# NNLightSwitcher_WirelessCharger.net
KiCad netlist of a schematic drawn in Altium Designer
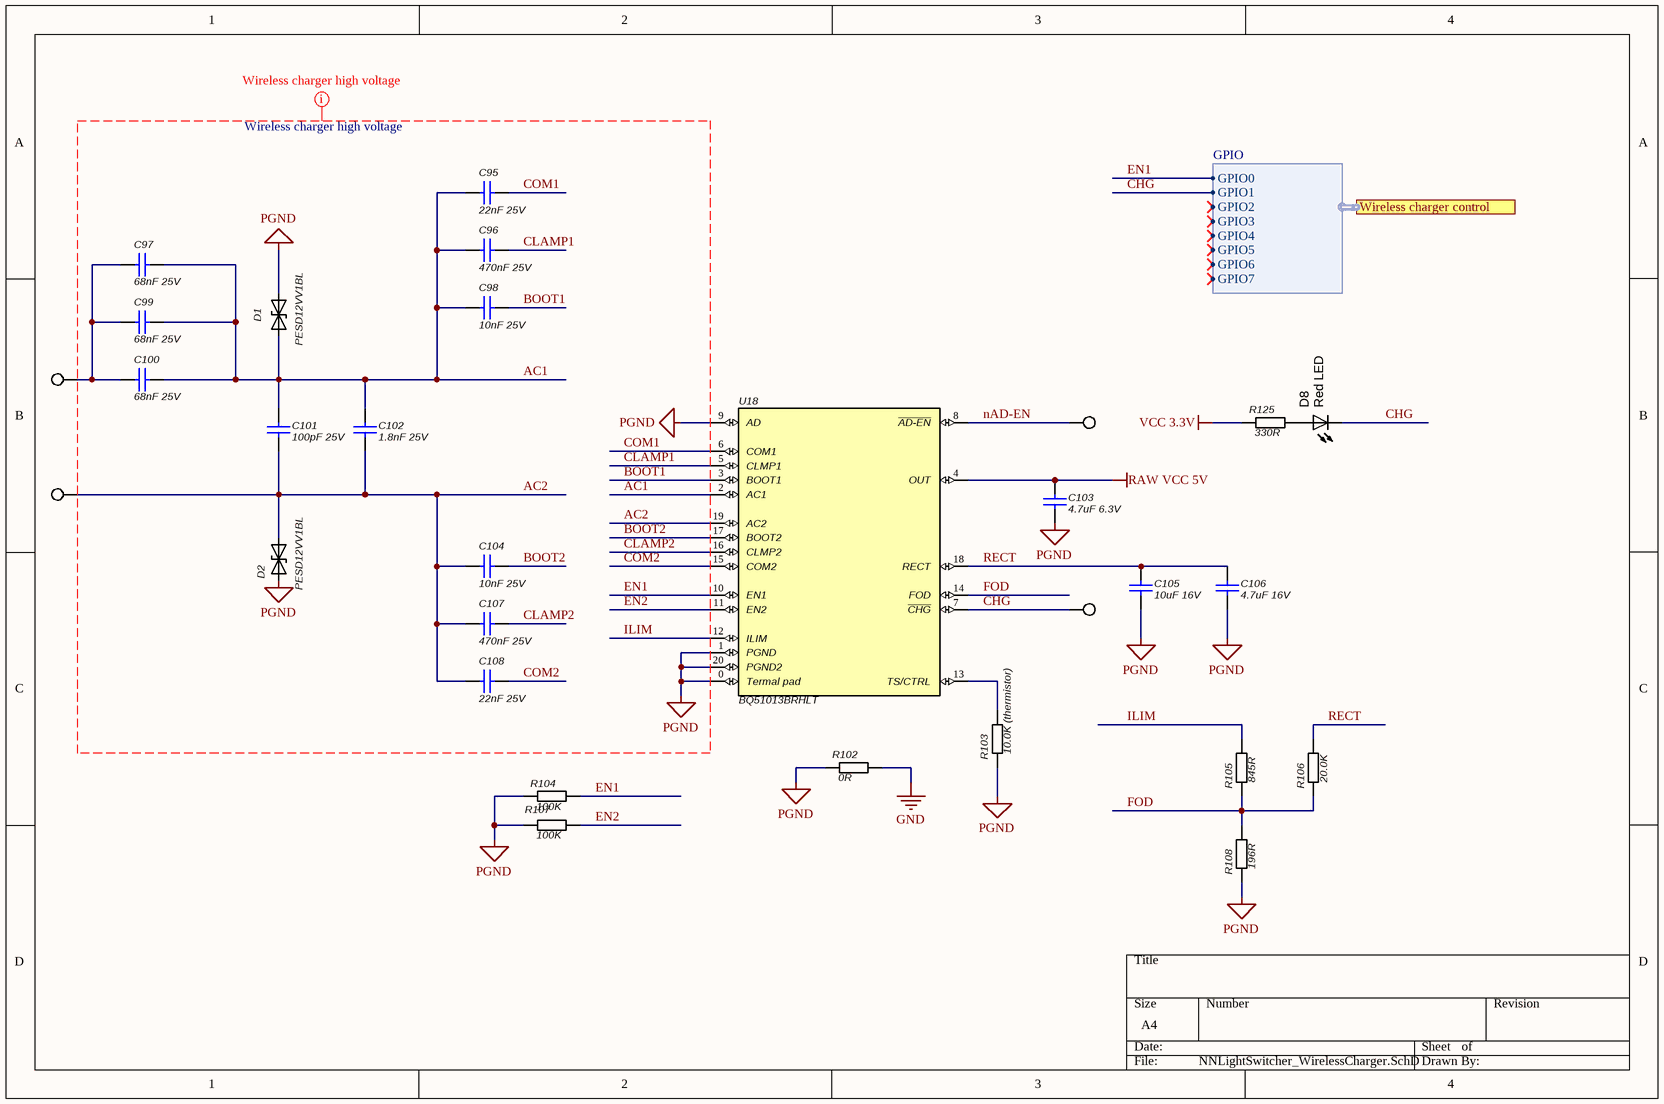
[diagram p0: NNLightSwitcher_WirelessCharger.SchDoc]

(export (version "E")
  (design (tool "Eeschema 10.0.6"))
  (components
    (comp (ref "C95")
      (value "22nF 25V")
      (footprint "0402")
      (description "GRM155R71E223KA61D")
      (fields (field (name "TOLERANCE") "10%") (field (name "VOLTAGE") "25V"))
      (libsource (lib "NNLightSwitcher") (part "Capacitor 22nF 25V"))
    )
    (comp (ref "C96")
      (value "470nF 25V")
      (footprint "0402")
      (description "GRM188R71E474KA12D")
      (fields (field (name "TOLERANCE") "10%") (field (name "VOLTAGE") "50V"))
      (libsource (lib "NNLightSwitcher") (part "Capacitor 470nF 25V"))
    )
    (comp (ref "C97")
      (value "68nF 25V")
      (footprint "*0603")
      (description "CAP CER 0.068UF 25V X7R 0603CC0603KRX7R8BB683")
      (fields (field (name "TOLERANCE") "10%") (field (name "VOLTAGE") "25V"))
      (libsource (lib "NNLightSwitcher") (part "Capacitor 68nF 25V"))
    )
    (comp (ref "C98")
      (value "10nF 25V")
      (footprint "0402")
      (description "GRM155R71E103KA01D")
      (fields (field (name "TOLERANCE") "10%") (field (name "VOLTAGE") "25V"))
      (libsource (lib "NNLightSwitcher") (part "Capacitor 10nF 25V"))
    )
    (comp (ref "C99")
      (value "68nF 25V")
      (footprint "*0603")
      (description "CAP CER 0.068UF 25V X7R 0603CC0603KRX7R8BB683")
      (fields (field (name "TOLERANCE") "10%") (field (name "VOLTAGE") "25V"))
      (libsource (lib "NNLightSwitcher") (part "Capacitor 68nF 25V"))
    )
    (comp (ref "C100")
      (value "68nF 25V")
      (footprint "*0603")
      (description "CAP CER 0.068UF 25V X7R 0603CC0603KRX7R8BB683")
      (fields (field (name "TOLERANCE") "10%") (field (name "VOLTAGE") "25V"))
      (libsource (lib "NNLightSwitcher") (part "Capacitor 68nF 25V"))
    )
    (comp (ref "C101")
      (value "100pF 25V")
      (footprint "0402")
      (description "GRM033R71E101KA01D")
      (fields (field (name "TOLERANCE") "10%") (field (name "VOLTAGE") "25V"))
      (libsource (lib "NNLightSwitcher") (part "Capacitor 100pF 25V"))
    )
    (comp (ref "C102")
      (value "1.8nF 25V")
      (footprint "0402")
      (description "GRM155R71H182KA01D")
      (fields (field (name "TOLERANCE") "10%") (field (name "VOLTAGE") "50V"))
      (libsource (lib "NNLightSwitcher") (part "Capacitor 1.8nF 50V"))
    )
    (comp (ref "C103")
      (value "4.7uF 6.3V")
      (footprint "*0603")
      (libsource (lib "NNLightSwitcher") (part "Capacitor 4.7uF 6.3V"))
    )
    (comp (ref "C104")
      (value "10nF 25V")
      (footprint "0402")
      (description "GRM155R71E103KA01D")
      (fields (field (name "TOLERANCE") "10%") (field (name "VOLTAGE") "25V"))
      (libsource (lib "NNLightSwitcher") (part "Capacitor 10nF 25V"))
    )
    (comp (ref "C105")
      (value "10uF 16V")
      (footprint "*0603")
      (description "EMK107BBJ106MA-T")
      (fields (field (name "TOLERANCE") "20%"))
      (libsource (lib "NNLightSwitcher") (part "Capacitor 10uF 16V"))
    )
    (comp (ref "C106")
      (value "4.7uF 16V")
      (footprint "*0603")
      (description "GRM188R61C475KAAJ")
      (fields (field (name "TOLERANCE") "10%"))
      (libsource (lib "NNLightSwitcher") (part "Capacitor 4.7uF 16V"))
    )
    (comp (ref "C107")
      (value "470nF 25V")
      (footprint "0402")
      (description "GRM188R71E474KA12D")
      (fields (field (name "TOLERANCE") "10%") (field (name "VOLTAGE") "50V"))
      (libsource (lib "NNLightSwitcher") (part "Capacitor 470nF 25V"))
    )
    (comp (ref "C108")
      (value "22nF 25V")
      (footprint "0402")
      (description "GRM155R71E223KA61D")
      (fields (field (name "TOLERANCE") "10%") (field (name "VOLTAGE") "25V"))
      (libsource (lib "NNLightSwitcher") (part "Capacitor 22nF 25V"))
    )
    (comp (ref "D1")
      (value "PESD12VV1BL")
      (footprint "*SOD882(T)")
      (description "ESD Suppressor TVS 30KV")
      (libsource (lib "NNLightSwitcher") (part "PESD12VV1BL"))
    )
    (comp (ref "D2")
      (value "PESD12VV1BL")
      (footprint "*SOD882(T)")
      (description "ESD Suppressor TVS 30KV")
      (libsource (lib "NNLightSwitcher") (part "PESD12VV1BL"))
    )
    (comp (ref "D8")
      (value "Red LED")
      (footprint "*LED_SML-P11UTT86R_SML-P11MTT86(Primary)")
      (description "LED red 0402")
      (libsource (lib "NNLightSwitcher") (part "APHHS1005SURCK"))
    )
    (comp (ref "R102")
      (value "0R")
      (footprint "0402")
      (libsource (lib "NNLightSwitcher") (part "Resistor 0R"))
    )
    (comp (ref "R103")
      (value "10.0K (thermistor)")
      (footprint "0402")
      (description "thermistor")
      (libsource (lib "NNLightSwitcher") (part "Resistor 10.0K"))
    )
    (comp (ref "R104")
      (value "100K")
      (footprint "0402")
      (libsource (lib "NNLightSwitcher") (part "Resistor 100K"))
    )
    (comp (ref "R105")
      (value "845R")
      (footprint "0402")
      (libsource (lib "NNLightSwitcher") (part "Resistor 845R"))
    )
    (comp (ref "R106")
      (value "20.0K")
      (footprint "0402")
      (libsource (lib "NNLightSwitcher") (part "Resistor 20.0K"))
    )
    (comp (ref "R107")
      (value "100K")
      (footprint "0402")
      (libsource (lib "NNLightSwitcher") (part "Resistor 100K"))
    )
    (comp (ref "R108")
      (value "196R")
      (footprint "0402")
      (libsource (lib "NNLightSwitcher") (part "Resistor 196R"))
    )
    (comp (ref "R125")
      (value "330R")
      (footprint "0402")
      (libsource (lib "NNLightSwitcher") (part "Resistor 330R"))
    )
    (comp (ref "TP56")
      (value "Test point")
      (footprint "Connection")
      (description "Test Point, Miniature, SMT")
      (libsource (lib "NNLightSwitcher") (part "Test point"))
    )
    (comp (ref "TP57")
      (value "Test point")
      (footprint "Testpoint_with_pad")
      (description "Test Point, Miniature, SMT")
      (libsource (lib "NNLightSwitcher") (part "Test point"))
    )
    (comp (ref "TP58")
      (value "Test point")
      (footprint "Connection")
      (description "Test Point, Miniature, SMT")
      (libsource (lib "NNLightSwitcher") (part "Test point"))
    )
    (comp (ref "TP59")
      (value "Test point")
      (footprint "Testpoint_Keystone_Miniature")
      (description "Test Point, Miniature, SMT")
      (libsource (lib "NNLightSwitcher") (part "Test point"))
    )
    (comp (ref "U18")
      (value "BQ51013BRHLT")
      (footprint "*QFN-20(VQFN-20)")
      (description "WPC 1.1 Compatible Fully Integrated Wireless Power Receiver IC 20-VQFN")
      (libsource (lib "NNLightSwitcher") (part "BQ51013BRHLT"))
    )
  )
  (nets
    (net (code "2") (name "/AC1") (class "Default")
      (node (ref "C100") (pin "1") (pinfunction "1_1") (pintype "passive"))
      (node (ref "C101") (pin "1") (pinfunction "1_1") (pintype "passive"))
      (node (ref "C102") (pin "1") (pinfunction "1_1") (pintype "passive"))
      (node (ref "C95") (pin "2") (pinfunction "2_2") (pintype "passive"))
      (node (ref "C96") (pin "2") (pinfunction "2_2") (pintype "passive"))
      (node (ref "C97") (pin "1") (pinfunction "1_1") (pintype "passive"))
      (node (ref "C98") (pin "2") (pinfunction "2_2") (pintype "passive"))
      (node (ref "C99") (pin "1") (pinfunction "1_1") (pintype "passive"))
      (node (ref "D1") (pin "2") (pinfunction "A_2") (pintype "passive"))
      (node (ref "U18") (pin "2") (pinfunction "AC1_2") (pintype "bidirectional"))
    )
    (net (code "3") (name "/AC2") (class "Default")
      (node (ref "C101") (pin "2") (pinfunction "2_2") (pintype "passive"))
      (node (ref "C102") (pin "2") (pinfunction "2_2") (pintype "passive"))
      (node (ref "C104") (pin "2") (pinfunction "2_2") (pintype "passive"))
      (node (ref "C107") (pin "2") (pinfunction "2_2") (pintype "passive"))
      (node (ref "C108") (pin "2") (pinfunction "2_2") (pintype "passive"))
      (node (ref "D2") (pin "1") (pinfunction "K_1") (pintype "passive"))
      (node (ref "TP58") (pin "1") (pintype "passive"))
      (node (ref "U18") (pin "19") (pinfunction "AC2_19") (pintype "bidirectional"))
    )
    (net (code "4") (name "/BOOT1") (class "Default")
      (node (ref "C98") (pin "1") (pinfunction "1_1") (pintype "passive"))
      (node (ref "U18") (pin "3") (pinfunction "BOOT1_3") (pintype "bidirectional"))
    )
    (net (code "5") (name "/BOOT2") (class "Default")
      (node (ref "C104") (pin "1") (pinfunction "1_1") (pintype "passive"))
      (node (ref "U18") (pin "17") (pinfunction "BOOT2_17") (pintype "bidirectional"))
    )
    (net (code "6") (name "/CHG") (class "Default")
      (node (ref "D8") (pin "C") (pinfunction "C_C") (pintype "passive"))
      (node (ref "TP59") (pin "1") (pintype "passive"))
      (node (ref "U18") (pin "7") (pinfunction "~{CHG}_7") (pintype "bidirectional"))
    )
    (net (code "7") (name "/CLAMP1") (class "Default")
      (node (ref "C96") (pin "1") (pinfunction "1_1") (pintype "passive"))
      (node (ref "U18") (pin "5") (pinfunction "CLMP1_5") (pintype "bidirectional"))
    )
    (net (code "8") (name "/CLAMP2") (class "Default")
      (node (ref "C107") (pin "1") (pinfunction "1_1") (pintype "passive"))
      (node (ref "U18") (pin "16") (pinfunction "CLMP2_16") (pintype "bidirectional"))
    )
    (net (code "9") (name "/COM1") (class "Default")
      (node (ref "C95") (pin "1") (pinfunction "1_1") (pintype "passive"))
      (node (ref "U18") (pin "6") (pinfunction "COM1_6") (pintype "bidirectional"))
    )
    (net (code "10") (name "/COM2") (class "Default")
      (node (ref "C108") (pin "1") (pinfunction "1_1") (pintype "passive"))
      (node (ref "U18") (pin "15") (pinfunction "COM2_15") (pintype "bidirectional"))
    )
    (net (code "11") (name "/EN1") (class "Default")
      (node (ref "R104") (pin "2") (pinfunction "2_2") (pintype "passive"))
      (node (ref "U18") (pin "10") (pinfunction "EN1_10") (pintype "bidirectional"))
    )
    (net (code "12") (name "/EN2") (class "Default")
      (node (ref "R107") (pin "2") (pinfunction "2_2") (pintype "passive"))
      (node (ref "U18") (pin "11") (pinfunction "EN2_11") (pintype "bidirectional"))
    )
    (net (code "13") (name "/FOD") (class "Default")
      (node (ref "R105") (pin "1") (pinfunction "1_1") (pintype "passive"))
      (node (ref "R106") (pin "1") (pinfunction "1_1") (pintype "passive"))
      (node (ref "R108") (pin "2") (pinfunction "2_2") (pintype "passive"))
      (node (ref "U18") (pin "14") (pinfunction "FOD_14") (pintype "bidirectional"))
    )
    (net (code "14") (name "/ILIM") (class "Default")
      (node (ref "R105") (pin "2") (pinfunction "2_2") (pintype "passive"))
      (node (ref "U18") (pin "12") (pinfunction "ILIM_12") (pintype "bidirectional"))
    )
    (net (code "15") (name "/RECT") (class "Default")
      (node (ref "C105") (pin "2") (pinfunction "2_2") (pintype "passive"))
      (node (ref "C106") (pin "1") (pinfunction "1_1") (pintype "passive"))
      (node (ref "R106") (pin "2") (pinfunction "2_2") (pintype "passive"))
      (node (ref "U18") (pin "18") (pinfunction "RECT_18") (pintype "bidirectional"))
    )
    (net (code "16") (name "/nAD-EN") (class "Default")
      (node (ref "TP57") (pin "1") (pintype "passive"))
      (node (ref "U18") (pin "8") (pinfunction "~{AD-EN}_8") (pintype "bidirectional"))
    )
    (net (code "18") (name "GND") (class "Default")
      (node (ref "R102") (pin "2") (pinfunction "2_2") (pintype "passive"))
    )
    (net (code "19") (name "Net-(C100-Pad2)") (class "Default")
      (node (ref "C100") (pin "2") (pinfunction "2_2") (pintype "passive"))
      (node (ref "C97") (pin "2") (pinfunction "2_2") (pintype "passive"))
      (node (ref "C99") (pin "2") (pinfunction "2_2") (pintype "passive"))
      (node (ref "TP56") (pin "1") (pintype "passive"))
    )
    (net (code "20") (name "Net-(D8-PadA)") (class "Default")
      (node (ref "D8") (pin "A") (pinfunction "A_A") (pintype "passive"))
      (node (ref "R125") (pin "2") (pinfunction "2_2") (pintype "passive"))
    )
    (net (code "21") (name "Net-(U18-TS{slash}CTRL)") (class "Default")
      (node (ref "R103") (pin "2") (pinfunction "2_2") (pintype "passive"))
      (node (ref "U18") (pin "13") (pinfunction "TS/CTRL_13") (pintype "bidirectional"))
    )
    (net (code "22") (name "PGND") (class "Default")
      (node (ref "C103") (pin "2") (pinfunction "2_2") (pintype "passive"))
      (node (ref "C105") (pin "1") (pinfunction "1_1") (pintype "passive"))
      (node (ref "C106") (pin "2") (pinfunction "2_2") (pintype "passive"))
      (node (ref "D1") (pin "1") (pinfunction "K_1") (pintype "passive"))
      (node (ref "D2") (pin "2") (pinfunction "A_2") (pintype "passive"))
      (node (ref "R102") (pin "1") (pinfunction "1_1") (pintype "passive"))
      (node (ref "R103") (pin "1") (pinfunction "1_1") (pintype "passive"))
      (node (ref "R104") (pin "1") (pinfunction "1_1") (pintype "passive"))
      (node (ref "R107") (pin "1") (pinfunction "1_1") (pintype "passive"))
      (node (ref "R108") (pin "1") (pinfunction "1_1") (pintype "passive"))
      (node (ref "U18") (pin "0") (pinfunction "Termal_pad_0") (pintype "bidirectional"))
      (node (ref "U18") (pin "1") (pinfunction "PGND_1") (pintype "bidirectional"))
      (node (ref "U18") (pin "20") (pinfunction "PGND2_20") (pintype "bidirectional"))
      (node (ref "U18") (pin "9") (pinfunction "AD_9") (pintype "bidirectional"))
    )
    (net (code "23") (name "RAW VCC 5V") (class "Default")
      (node (ref "C103") (pin "1") (pinfunction "1_1") (pintype "passive"))
      (node (ref "U18") (pin "4") (pinfunction "OUT_4") (pintype "bidirectional"))
    )
    (net (code "24") (name "VCC 3.3V") (class "Default")
      (node (ref "R125") (pin "1") (pinfunction "1_1") (pintype "passive"))
    )
  )
)
